# CT_Metering_Assignment-V_33_error_checke.net
KiCad netlist of a schematic drawn in EAGLE
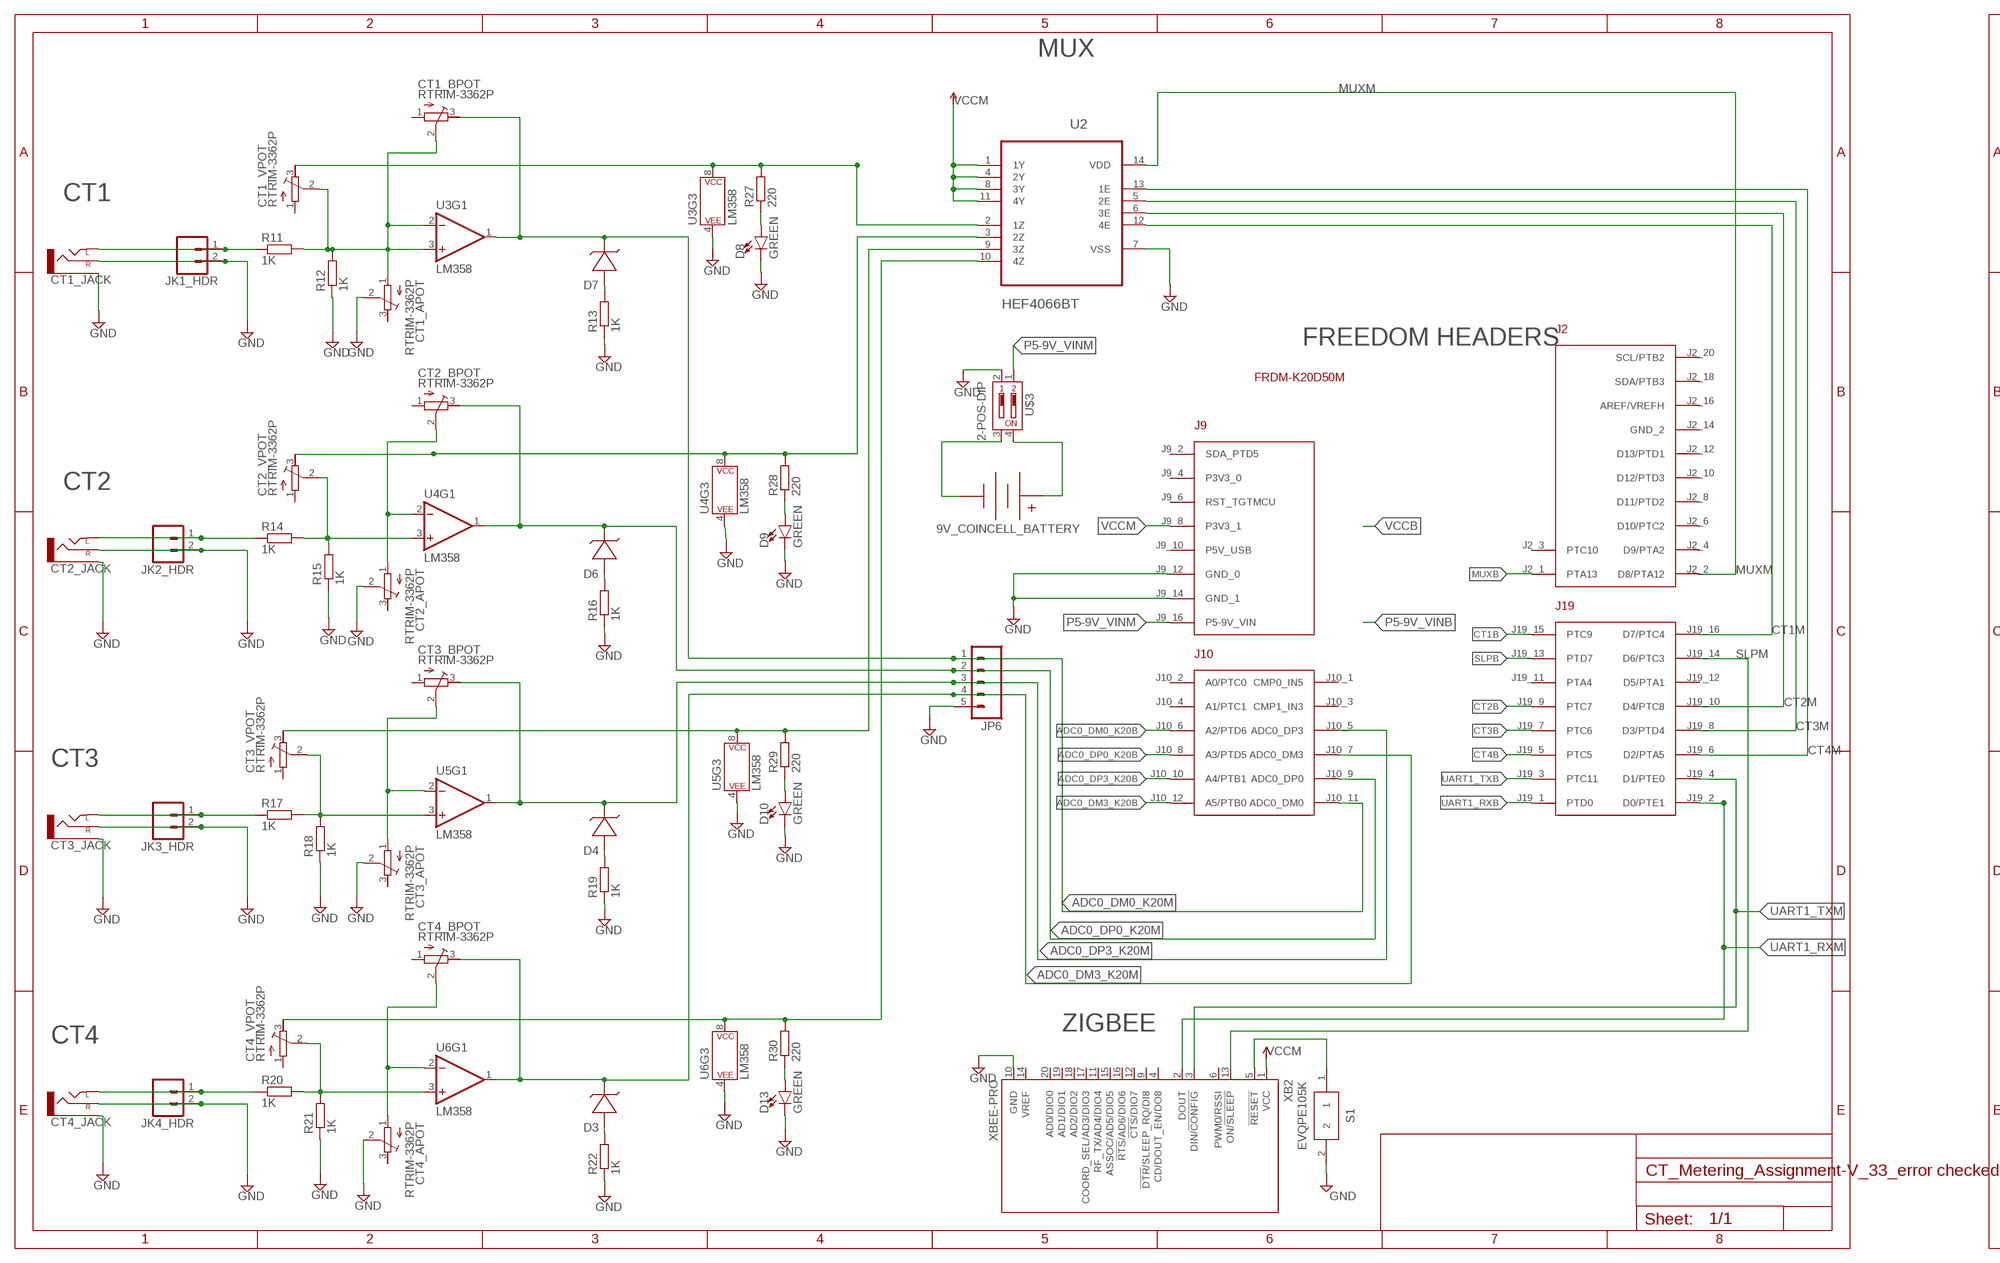
[diagram p0: schematic, sheet 1, part 1 of 2]
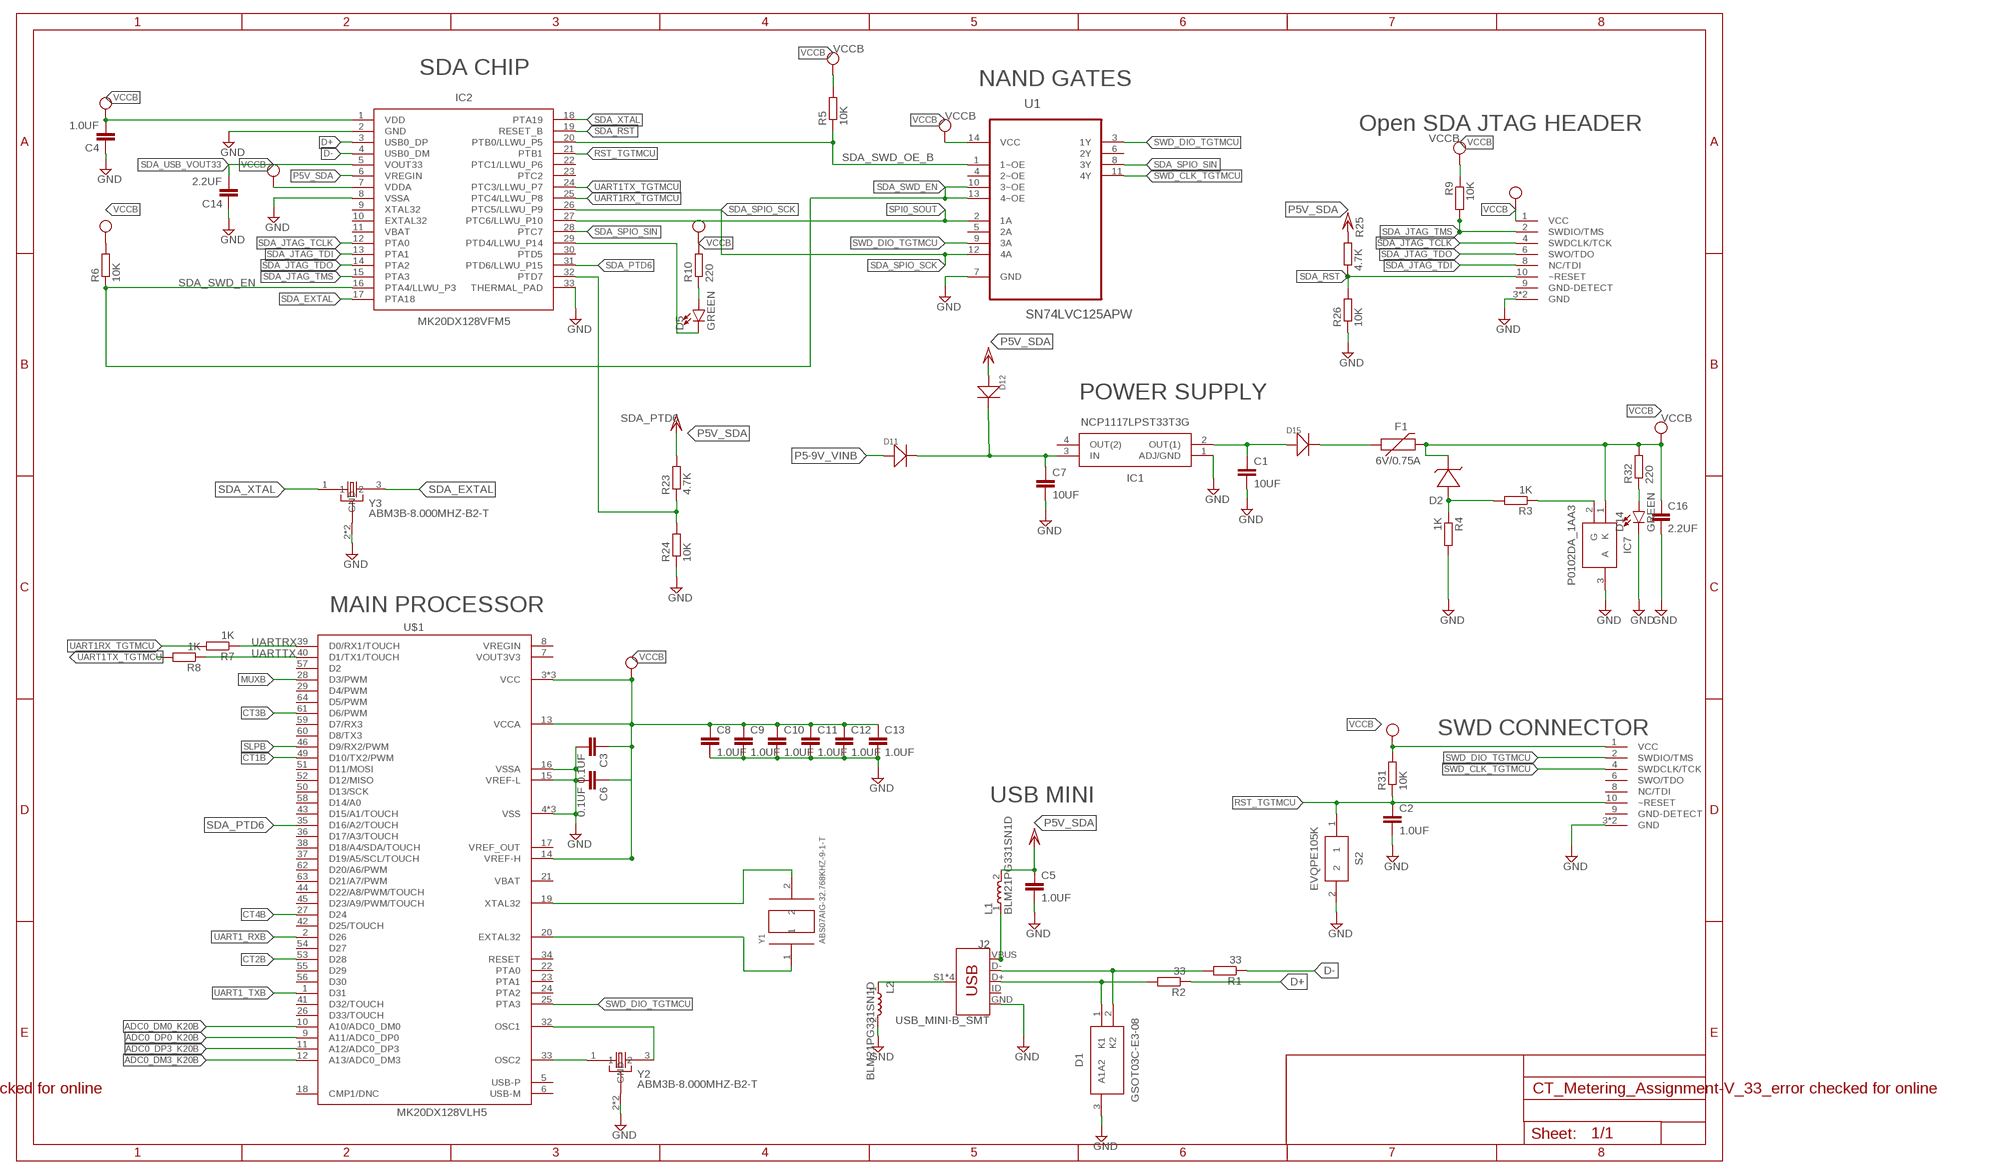
[diagram p1: schematic, sheet 1, part 2 of 2]

(export (version "E")
  (design (tool "Eeschema 10.0.6"))
  (components
    (comp (ref "9V_COINCELL_BATTERY")
      (value "BC9VPC")
      (footprint "eagle-import:BC9VPC")
      (libsource (lib "eagle-import") (part "BC9VPC"))
    )
    (comp (ref "C1")
      (value "10UF")
      (footprint "eagle-import:C1210")
      (libsource (lib "eagle-import") (part "CC1210"))
    )
    (comp (ref "C2")
      (value "1.0UF")
      (footprint "eagle-import:C1210")
      (libsource (lib "eagle-import") (part "CC1210"))
    )
    (comp (ref "C3")
      (value "0.1UF")
      (footprint "eagle-import:C1210")
      (libsource (lib "eagle-import") (part "CC1210"))
    )
    (comp (ref "C4")
      (value "1.0UF")
      (footprint "eagle-import:C1210")
      (libsource (lib "eagle-import") (part "CC1210"))
    )
    (comp (ref "C5")
      (value "1.0UF")
      (footprint "eagle-import:C1210")
      (libsource (lib "eagle-import") (part "CC1210"))
    )
    (comp (ref "C6")
      (value "0.1UF")
      (footprint "eagle-import:C1210")
      (libsource (lib "eagle-import") (part "CC1210"))
    )
    (comp (ref "C7")
      (value "10UF")
      (footprint "eagle-import:C1210")
      (libsource (lib "eagle-import") (part "CC1210"))
    )
    (comp (ref "C8")
      (value "1.0UF")
      (footprint "eagle-import:C1210")
      (libsource (lib "eagle-import") (part "CC1210"))
    )
    (comp (ref "C9")
      (value "1.0UF")
      (footprint "eagle-import:C1210")
      (libsource (lib "eagle-import") (part "CC1210"))
    )
    (comp (ref "C10")
      (value "1.0UF")
      (footprint "eagle-import:C1210")
      (libsource (lib "eagle-import") (part "CC1210"))
    )
    (comp (ref "C11")
      (value "1.0UF")
      (footprint "eagle-import:C1210")
      (libsource (lib "eagle-import") (part "CC1210"))
    )
    (comp (ref "C12")
      (value "1.0UF")
      (footprint "eagle-import:C1210")
      (libsource (lib "eagle-import") (part "CC1210"))
    )
    (comp (ref "C13")
      (value "1.0UF")
      (footprint "eagle-import:C1210")
      (libsource (lib "eagle-import") (part "CC1210"))
    )
    (comp (ref "C14")
      (value "2.2UF")
      (footprint "eagle-import:C1210")
      (libsource (lib "eagle-import") (part "CC1210"))
    )
    (comp (ref "C16")
      (value "2.2UF")
      (footprint "eagle-import:C1210")
      (libsource (lib "eagle-import") (part "CC1210"))
    )
    (comp (ref "CT1_APOT")
      (value "RTRIM-3362P")
      (footprint "eagle-import:RTRIM3362P")
      (libsource (lib "eagle-import") (part "RTRIM-3362P"))
    )
    (comp (ref "CT1_BPOT")
      (value "RTRIM-3362P")
      (footprint "eagle-import:RTRIM3362P")
      (libsource (lib "eagle-import") (part "RTRIM-3362P"))
    )
    (comp (ref "CT1_JACK")
      (value "AUDIO-JACKPTH")
      (footprint "eagle-import:AUDIO-JACK")
      (libsource (lib "eagle-import") (part "AUDIO-JACKPTH"))
    )
    (comp (ref "CT1_VPOT")
      (value "RTRIM-3362P")
      (footprint "eagle-import:RTRIM3362P")
      (libsource (lib "eagle-import") (part "RTRIM-3362P"))
    )
    (comp (ref "CT2_APOT")
      (value "RTRIM-3362P")
      (footprint "eagle-import:RTRIM3362P")
      (libsource (lib "eagle-import") (part "RTRIM-3362P"))
    )
    (comp (ref "CT2_BPOT")
      (value "RTRIM-3362P")
      (footprint "eagle-import:RTRIM3362P")
      (libsource (lib "eagle-import") (part "RTRIM-3362P"))
    )
    (comp (ref "CT2_JACK")
      (value "AUDIO-JACKPTH")
      (footprint "eagle-import:AUDIO-JACK")
      (libsource (lib "eagle-import") (part "AUDIO-JACKPTH"))
    )
    (comp (ref "CT2_VPOT")
      (value "RTRIM-3362P")
      (footprint "eagle-import:RTRIM3362P")
      (libsource (lib "eagle-import") (part "RTRIM-3362P"))
    )
    (comp (ref "CT3_APOT")
      (value "RTRIM-3362P")
      (footprint "eagle-import:RTRIM3362P")
      (libsource (lib "eagle-import") (part "RTRIM-3362P"))
    )
    (comp (ref "CT3_BPOT")
      (value "RTRIM-3362P")
      (footprint "eagle-import:RTRIM3362P")
      (libsource (lib "eagle-import") (part "RTRIM-3362P"))
    )
    (comp (ref "CT3_JACK")
      (value "AUDIO-JACKPTH")
      (footprint "eagle-import:AUDIO-JACK")
      (libsource (lib "eagle-import") (part "AUDIO-JACKPTH"))
    )
    (comp (ref "CT3_VPOT")
      (value "RTRIM-3362P")
      (footprint "eagle-import:RTRIM3362P")
      (libsource (lib "eagle-import") (part "RTRIM-3362P"))
    )
    (comp (ref "CT4_APOT")
      (value "RTRIM-3362P")
      (footprint "eagle-import:RTRIM3362P")
      (libsource (lib "eagle-import") (part "RTRIM-3362P"))
    )
    (comp (ref "CT4_BPOT")
      (value "RTRIM-3362P")
      (footprint "eagle-import:RTRIM3362P")
      (libsource (lib "eagle-import") (part "RTRIM-3362P"))
    )
    (comp (ref "CT4_JACK")
      (value "AUDIO-JACKPTH")
      (footprint "eagle-import:AUDIO-JACK")
      (libsource (lib "eagle-import") (part "AUDIO-JACKPTH"))
    )
    (comp (ref "CT4_VPOT")
      (value "RTRIM-3362P")
      (footprint "eagle-import:RTRIM3362P")
      (libsource (lib "eagle-import") (part "RTRIM-3362P"))
    )
    (comp (ref "D1")
      (value "GSOT03C-E3-08")
      (footprint "eagle-import:SOT100P248X115-3N")
      (fields (field (name "RS_PART_NUMBER") "6997957"))
      (libsource (lib "eagle-import") (part "GSOT03C-E3-08"))
    )
    (comp (ref "D2")
      (value "ZENER")
      (footprint "eagle-import:SOD123")
      (libsource (lib "eagle-import") (part "ZENER"))
    )
    (comp (ref "D3")
      (value "ZENER")
      (footprint "eagle-import:SOD123")
      (libsource (lib "eagle-import") (part "ZENER"))
    )
    (comp (ref "D4")
      (value "ZENER")
      (footprint "eagle-import:SOD123")
      (libsource (lib "eagle-import") (part "ZENER"))
    )
    (comp (ref "D5")
      (value "GREEN")
      (footprint "eagle-import:LED-0603")
      (libsource (lib "eagle-import") (part "LED-GREEN0603"))
    )
    (comp (ref "D6")
      (value "ZENER")
      (footprint "eagle-import:SOD123")
      (libsource (lib "eagle-import") (part "ZENER"))
    )
    (comp (ref "D7")
      (value "ZENER")
      (footprint "eagle-import:SOD123")
      (libsource (lib "eagle-import") (part "ZENER"))
    )
    (comp (ref "D8")
      (value "GREEN")
      (footprint "eagle-import:LED-0603")
      (libsource (lib "eagle-import") (part "LED-GREEN0603"))
    )
    (comp (ref "D9")
      (value "GREEN")
      (footprint "eagle-import:LED-0603")
      (libsource (lib "eagle-import") (part "LED-GREEN0603"))
    )
    (comp (ref "D10")
      (value "GREEN")
      (footprint "eagle-import:LED-0603")
      (libsource (lib "eagle-import") (part "LED-GREEN0603"))
    )
    (comp (ref "D11")
      (value "20V-1A")
      (footprint "eagle-import:SOD-123")
      (fields (field (name "MPN") "B5819W"))
      (libsource (lib "eagle-import") (part "SMD-DIODE-SCHOTTKY-20V-1A(SOD-123)"))
    )
    (comp (ref "D12")
      (value "20V-1A")
      (footprint "eagle-import:SOD-123")
      (fields (field (name "MPN") "B5819W"))
      (libsource (lib "eagle-import") (part "SMD-DIODE-SCHOTTKY-20V-1A(SOD-123)"))
    )
    (comp (ref "D13")
      (value "GREEN")
      (footprint "eagle-import:LED-0603")
      (libsource (lib "eagle-import") (part "LED-GREEN0603"))
    )
    (comp (ref "D14")
      (value "GREEN")
      (footprint "eagle-import:LED-0603")
      (libsource (lib "eagle-import") (part "LED-GREEN0603"))
    )
    (comp (ref "D15")
      (value "20V-1A")
      (footprint "eagle-import:SOD-123")
      (fields (field (name "MPN") "B5819W"))
      (libsource (lib "eagle-import") (part "SMD-DIODE-SCHOTTKY-20V-1A(SOD-123)"))
    )
    (comp (ref "F1")
      (value "6V/0.75A")
      (footprint "eagle-import:1206")
      (libsource (lib "eagle-import") (part "PPTC_THREE-QUARTER-AMP"))
    )
    (comp (ref "FRDM1")
      (value "FRDM-K20D50M")
      (footprint "eagle-import:FRDM-K20D50M")
      (libsource (lib "eagle-import") (part "FRDM-K20D50M"))
    )
    (comp (ref "IC1")
      (value "NCP1117LPST33T3G")
      (footprint "eagle-import:SOT230P700X180-4N")
      (fields (field (name "RS_PART_NUMBER") "1245347"))
      (libsource (lib "eagle-import") (part "NCP1117LPST33T3G"))
    )
    (comp (ref "IC2")
      (value "MK20DX128VFM5")
      (footprint "eagle-import:SOT617-14")
      (fields (field (name "RS_PART_NUMBER") "8181223"))
      (libsource (lib "eagle-import") (part "MK20DX128VFM5"))
    )
    (comp (ref "IC7")
      (value "P0102DA_1AA3")
      (footprint "eagle-import:TO-92")
      (fields
        (field (name "MANUFACTURER_PART_NUMBER") "P0102DA 1AA3")
        (field (name "RS_PART_NUMBER") "7142647")
      )
      (libsource (lib "eagle-import") (part "P0102DA_1AA3"))
    )
    (comp (ref "J2")
      (value "USB_MINI-B_SMT")
      (footprint "eagle-import:USB-MINIB")
      (libsource (lib "eagle-import") (part "USB_MINI-B_SMT"))
    )
    (comp (ref "JK1_HDR")
      (value "M02PTH")
      (footprint "eagle-import:1X02")
      (libsource (lib "eagle-import") (part "M02PTH"))
    )
    (comp (ref "JK2_HDR")
      (value "M02PTH")
      (footprint "eagle-import:1X02")
      (libsource (lib "eagle-import") (part "M02PTH"))
    )
    (comp (ref "JK3_HDR")
      (value "M02PTH")
      (footprint "eagle-import:1X02")
      (libsource (lib "eagle-import") (part "M02PTH"))
    )
    (comp (ref "JK4_HDR")
      (value "M02PTH")
      (footprint "eagle-import:1X02")
      (libsource (lib "eagle-import") (part "M02PTH"))
    )
    (comp (ref "JP6")
      (value "M05PTH")
      (footprint "eagle-import:1X05")
      (libsource (lib "eagle-import") (part "M05PTH"))
    )
    (comp (ref "L1")
      (value "BLM21PG331SN1D")
      (footprint "eagle-import:INDC2012X87")
      (fields (field (name "MF") "Murata"))
      (libsource (lib "eagle-import") (part "BLM21PG331SN1D"))
    )
    (comp (ref "L2")
      (value "BLM21PG331SN1D")
      (footprint "eagle-import:INDC2012X87")
      (fields (field (name "MF") "Murata"))
      (libsource (lib "eagle-import") (part "BLM21PG331SN1D"))
    )
    (comp (ref "R1")
      (value "33")
      (footprint "eagle-import:PRL1632")
      (libsource (lib "eagle-import") (part "R-EU_PRL1632"))
    )
    (comp (ref "R2")
      (value "33")
      (footprint "eagle-import:PRL1632")
      (libsource (lib "eagle-import") (part "R-EU_PRL1632"))
    )
    (comp (ref "R3")
      (value "1K")
      (footprint "eagle-import:PRL1632")
      (libsource (lib "eagle-import") (part "R-EU_PRL1632"))
    )
    (comp (ref "R4")
      (value "1K")
      (footprint "eagle-import:PRL1632")
      (libsource (lib "eagle-import") (part "R-EU_PRL1632"))
    )
    (comp (ref "R5")
      (value "10K")
      (footprint "eagle-import:PRL1632")
      (libsource (lib "eagle-import") (part "R-EU_PRL1632"))
    )
    (comp (ref "R6")
      (value "10K")
      (footprint "eagle-import:PRL1632")
      (libsource (lib "eagle-import") (part "R-EU_PRL1632"))
    )
    (comp (ref "R7")
      (value "1K")
      (footprint "eagle-import:PRL1632")
      (libsource (lib "eagle-import") (part "R-EU_PRL1632"))
    )
    (comp (ref "R8")
      (value "1K")
      (footprint "eagle-import:PRL1632")
      (libsource (lib "eagle-import") (part "R-EU_PRL1632"))
    )
    (comp (ref "R9")
      (value "10K")
      (footprint "eagle-import:PRL1632")
      (libsource (lib "eagle-import") (part "R-EU_PRL1632"))
    )
    (comp (ref "R10")
      (value "220")
      (footprint "eagle-import:PRL1632")
      (libsource (lib "eagle-import") (part "R-EU_PRL1632"))
    )
    (comp (ref "R11")
      (value "1K")
      (footprint "eagle-import:PRL1632")
      (libsource (lib "eagle-import") (part "R-EU_PRL1632"))
    )
    (comp (ref "R12")
      (value "1K")
      (footprint "eagle-import:PRL1632")
      (libsource (lib "eagle-import") (part "R-EU_PRL1632"))
    )
    (comp (ref "R13")
      (value "1K")
      (footprint "eagle-import:PRL1632")
      (libsource (lib "eagle-import") (part "R-EU_PRL1632"))
    )
    (comp (ref "R14")
      (value "1K")
      (footprint "eagle-import:PRL1632")
      (libsource (lib "eagle-import") (part "R-EU_PRL1632"))
    )
    (comp (ref "R15")
      (value "1K")
      (footprint "eagle-import:PRL1632")
      (libsource (lib "eagle-import") (part "R-EU_PRL1632"))
    )
    (comp (ref "R16")
      (value "1K")
      (footprint "eagle-import:PRL1632")
      (libsource (lib "eagle-import") (part "R-EU_PRL1632"))
    )
    (comp (ref "R17")
      (value "1K")
      (footprint "eagle-import:PRL1632")
      (libsource (lib "eagle-import") (part "R-EU_PRL1632"))
    )
    (comp (ref "R18")
      (value "1K")
      (footprint "eagle-import:PRL1632")
      (libsource (lib "eagle-import") (part "R-EU_PRL1632"))
    )
    (comp (ref "R19")
      (value "1K")
      (footprint "eagle-import:PRL1632")
      (libsource (lib "eagle-import") (part "R-EU_PRL1632"))
    )
    (comp (ref "R20")
      (value "1K")
      (footprint "eagle-import:PRL1632")
      (libsource (lib "eagle-import") (part "R-EU_PRL1632"))
    )
    (comp (ref "R21")
      (value "1K")
      (footprint "eagle-import:PRL1632")
      (libsource (lib "eagle-import") (part "R-EU_PRL1632"))
    )
    (comp (ref "R22")
      (value "1K")
      (footprint "eagle-import:PRL1632")
      (libsource (lib "eagle-import") (part "R-EU_PRL1632"))
    )
    (comp (ref "R23")
      (value "4.7K")
      (footprint "eagle-import:PRL1632")
      (libsource (lib "eagle-import") (part "R-EU_PRL1632"))
    )
    (comp (ref "R24")
      (value "10K")
      (footprint "eagle-import:PRL1632")
      (libsource (lib "eagle-import") (part "R-EU_PRL1632"))
    )
    (comp (ref "R25")
      (value "4.7K")
      (footprint "eagle-import:PRL1632")
      (libsource (lib "eagle-import") (part "R-EU_PRL1632"))
    )
    (comp (ref "R26")
      (value "10K")
      (footprint "eagle-import:PRL1632")
      (libsource (lib "eagle-import") (part "R-EU_PRL1632"))
    )
    (comp (ref "R27")
      (value "220")
      (footprint "eagle-import:PRL1632")
      (libsource (lib "eagle-import") (part "R-EU_PRL1632"))
    )
    (comp (ref "R28")
      (value "220")
      (footprint "eagle-import:PRL1632")
      (libsource (lib "eagle-import") (part "R-EU_PRL1632"))
    )
    (comp (ref "R29")
      (value "220")
      (footprint "eagle-import:PRL1632")
      (libsource (lib "eagle-import") (part "R-EU_PRL1632"))
    )
    (comp (ref "R30")
      (value "220")
      (footprint "eagle-import:PRL1632")
      (libsource (lib "eagle-import") (part "R-EU_PRL1632"))
    )
    (comp (ref "R31")
      (value "10K")
      (footprint "eagle-import:PRL1632")
      (libsource (lib "eagle-import") (part "R-EU_PRL1632"))
    )
    (comp (ref "R32")
      (value "220")
      (footprint "eagle-import:PRL1632")
      (libsource (lib "eagle-import") (part "R-EU_PRL1632"))
    )
    (comp (ref "S1")
      (value "EVQPE105K")
      (footprint "eagle-import:EVQPE1")
      (fields (field (name "RS_PART_NUMBER") "7561669"))
      (libsource (lib "eagle-import") (part "EVQPE105K"))
    )
    (comp (ref "S2")
      (value "EVQPE105K")
      (footprint "eagle-import:EVQPE1")
      (fields (field (name "RS_PART_NUMBER") "7561669"))
      (libsource (lib "eagle-import") (part "EVQPE105K"))
    )
    (comp (ref "U$1")
      (value "MK20DX128VLH5")
      (footprint "eagle-import:QFP50P1200X1200X160-64N")
      (fields (field (name "MF") "NXP Semiconductors"))
      (libsource (lib "eagle-import") (part "MK20DX128VLH5"))
    )
    (comp (ref "U$2")
      (value "2X5_0.05\"_CORTEX_DEBUGTH_NOKEY_UNSHROUDED")
      (footprint "eagle-import:2X5_0.05__TH_NS")
      (libsource (lib "eagle-import") (part "2X5_0.05{dblquote}_CORTEX_DEBUGTH_NOKEY_UNSHROUDED"))
    )
    (comp (ref "U$3")
      (value "2-POS-DIP")
      (footprint "eagle-import:CHS-02A")
      (libsource (lib "eagle-import") (part "2-POS-DIP"))
    )
    (comp (ref "U$6")
      (value "SWD HHEADER")
      (footprint "eagle-import:2X5_0.05__TH_NS")
      (libsource (lib "eagle-import") (part "2X5_0.05{dblquote}_CORTEX_DEBUGTH_NOKEY_UNSHROUDED"))
    )
    (comp (ref "U1")
      (value "SN74LVC125APW")
      (footprint "eagle-import:SOP65P640X120-14N")
      (fields (field (name "MF") "Texas Instruments"))
      (libsource (lib "eagle-import") (part "SN74LVC125APW"))
    )
    (comp (ref "U2")
      (value "HEF4066BT")
      (footprint "eagle-import:SOIC127P600X175-14N")
      (fields (field (name "MF") "NXP Semiconductors"))
      (libsource (lib "eagle-import") (part "HEF4066BT"))
    )
    (comp (ref "U3")
      (value "LM358")
      (footprint "eagle-import:DIP08")
      (libsource (lib "eagle-import") (part "LM358"))
    )
    (comp (ref "U4")
      (value "LM358")
      (footprint "eagle-import:DIP08")
      (libsource (lib "eagle-import") (part "LM358"))
    )
    (comp (ref "U5")
      (value "LM358")
      (footprint "eagle-import:DIP08")
      (libsource (lib "eagle-import") (part "LM358"))
    )
    (comp (ref "U6")
      (value "LM358")
      (footprint "eagle-import:DIP08")
      (libsource (lib "eagle-import") (part "LM358"))
    )
    (comp (ref "XB2")
      (value "XBEE-PRO")
      (footprint "eagle-import:XBEE-PRO")
      (fields (field (name "MPN") "XBP24-AWI-001"))
      (libsource (lib "eagle-import") (part "XBEE-PRO"))
    )
    (comp (ref "Y1")
      (value "ABS07AIG-32.768KHZ-9-1-T")
      (footprint "eagle-import:XTAL320X150X90")
      (fields (field (name "MF") "Abracon"))
      (libsource (lib "eagle-import") (part "ABS07AIG-32.768KHZ-9-1-T"))
    )
    (comp (ref "Y2")
      (value "ABM3B-8.000MHZ-B2-T")
      (footprint "eagle-import:OSCSC500X320X110-4N")
      (fields (field (name "MF") "Abracon"))
      (libsource (lib "eagle-import") (part "ABM3B-8.000MHZ-B2-T"))
    )
    (comp (ref "Y3")
      (value "ABM3B-8.000MHZ-B2-T")
      (footprint "eagle-import:OSCSC500X320X110-4N")
      (fields (field (name "MF") "Abracon"))
      (libsource (lib "eagle-import") (part "ABM3B-8.000MHZ-B2-T"))
    )
  )
  (nets
    (net (code "1") (name "/CT1M") (class "Default")
      (node (ref "FRDM1") (pin "J19_16") (pinfunction "D7/PTC4_J19_16") (pintype "bidirectional"))
      (node (ref "U2") (pin "12") (pinfunction "4E_12") (pintype "input"))
    )
    (net (code "2") (name "/CT2M") (class "Default")
      (node (ref "FRDM1") (pin "J19_10") (pinfunction "D4/PTC8_J19_10") (pintype "bidirectional"))
      (node (ref "U2") (pin "6") (pinfunction "3E_6") (pintype "input"))
    )
    (net (code "3") (name "/CT3M") (class "Default")
      (node (ref "FRDM1") (pin "J19_8") (pinfunction "D3/PTD4_J19_8") (pintype "bidirectional"))
      (node (ref "U2") (pin "5") (pinfunction "2E_5") (pintype "input"))
    )
    (net (code "4") (name "/CT4M") (class "Default")
      (node (ref "FRDM1") (pin "J19_6") (pinfunction "D2/PTA5_J19_6") (pintype "bidirectional"))
      (node (ref "U2") (pin "13") (pinfunction "1E_13") (pintype "input"))
    )
    (net (code "5") (name "/MUXM") (class "Default")
      (node (ref "FRDM1") (pin "J2_2") (pinfunction "D8/PTA12_J2_2") (pintype "bidirectional"))
      (node (ref "U2") (pin "14") (pinfunction "VDD_14") (pintype "power_in"))
    )
    (net (code "6") (name "/SDA_SWD_OE_B") (class "Default")
      (node (ref "IC2") (pin "20") (pinfunction "PTB0/LLWU_P5_20") (pintype "passive"))
      (node (ref "R5") (pin "1") (pinfunction "1_1") (pintype "passive"))
      (node (ref "U1") (pin "1") (pinfunction "1~{OE}_1") (pintype "input"))
    )
    (net (code "7") (name "/SLPM") (class "Default")
      (node (ref "FRDM1") (pin "J19_14") (pinfunction "D6/PTC3_J19_14") (pintype "bidirectional"))
      (node (ref "XB2") (pin "13") (pinfunction "ON/~{SLEEP}_13") (pintype "output"))
    )
    (net (code "8") (name "/UARTRX") (class "Default")
      (node (ref "R7") (pin "1") (pinfunction "1_1") (pintype "passive"))
      (node (ref "U$1") (pin "39") (pinfunction "D0/RX1/TOUCH_39") (pintype "bidirectional"))
    )
    (net (code "9") (name "/UARTTX") (class "Default")
      (node (ref "R8") (pin "1") (pinfunction "1_1") (pintype "passive"))
      (node (ref "U$1") (pin "40") (pinfunction "D1/TX1/TOUCH_40") (pintype "bidirectional"))
    )
    (net (code "10") (name "ADC0_DM0_K20B") (class "Default")
      (node (ref "FRDM1") (pin "J10_6") (pinfunction "A2/PTD6_J10_6") (pintype "bidirectional"))
      (node (ref "U$1") (pin "10") (pinfunction "A10/ADC0_DM0_10") (pintype "bidirectional"))
    )
    (net (code "11") (name "ADC0_DM0_K20M") (class "Default")
      (node (ref "CT1_BPOT") (pin "3") (pinfunction "3_3") (pintype "passive"))
      (node (ref "D7") (pin "C") (pinfunction "-_C") (pintype "passive"))
      (node (ref "FRDM1") (pin "J10_11") (pinfunction "ADC0_DM0_J10_11") (pintype "bidirectional"))
      (node (ref "JP6") (pin "1") (pinfunction "1_1") (pintype "passive"))
      (node (ref "U3") (pin "1") (pinfunction "OUT_1") (pintype "output"))
    )
    (net (code "12") (name "ADC0_DM3_K20B") (class "Default")
      (node (ref "FRDM1") (pin "J10_12") (pinfunction "A5/PTB0_J10_12") (pintype "bidirectional"))
      (node (ref "U$1") (pin "12") (pinfunction "A13/ADC0_DM3_12") (pintype "bidirectional"))
    )
    (net (code "13") (name "ADC0_DM3_K20M") (class "Default")
      (node (ref "CT4_BPOT") (pin "3") (pinfunction "3_3") (pintype "passive"))
      (node (ref "D3") (pin "C") (pinfunction "-_C") (pintype "passive"))
      (node (ref "FRDM1") (pin "J10_7") (pinfunction "ADC0_DM3_J10_7") (pintype "bidirectional"))
      (node (ref "JP6") (pin "4") (pinfunction "4_4") (pintype "passive"))
      (node (ref "U6") (pin "1") (pinfunction "OUT_1") (pintype "output"))
    )
    (net (code "14") (name "ADC0_DP0_K20B") (class "Default")
      (node (ref "FRDM1") (pin "J10_8") (pinfunction "A3/PTD5_J10_8") (pintype "bidirectional"))
      (node (ref "U$1") (pin "9") (pinfunction "A11/ADC0_DP0_9") (pintype "bidirectional"))
    )
    (net (code "15") (name "ADC0_DP0_K20M") (class "Default")
      (node (ref "CT2_BPOT") (pin "3") (pinfunction "3_3") (pintype "passive"))
      (node (ref "D6") (pin "C") (pinfunction "-_C") (pintype "passive"))
      (node (ref "FRDM1") (pin "J10_9") (pinfunction "ADC0_DP0_J10_9") (pintype "bidirectional"))
      (node (ref "JP6") (pin "2") (pinfunction "2_2") (pintype "passive"))
      (node (ref "U4") (pin "1") (pinfunction "OUT_1") (pintype "output"))
    )
    (net (code "16") (name "ADC0_DP3_K20B") (class "Default")
      (node (ref "FRDM1") (pin "J10_10") (pinfunction "A4/PTB1_J10_10") (pintype "bidirectional"))
      (node (ref "U$1") (pin "11") (pinfunction "A12/ADC0_DP3_11") (pintype "bidirectional"))
    )
    (net (code "17") (name "ADC0_DP3_K20M") (class "Default")
      (node (ref "CT3_BPOT") (pin "3") (pinfunction "3_3") (pintype "passive"))
      (node (ref "D4") (pin "C") (pinfunction "-_C") (pintype "passive"))
      (node (ref "FRDM1") (pin "J10_5") (pinfunction "ADC0_DP3_J10_5") (pintype "bidirectional"))
      (node (ref "JP6") (pin "3") (pinfunction "3_3") (pintype "passive"))
      (node (ref "U5") (pin "1") (pinfunction "OUT_1") (pintype "output"))
    )
    (net (code "18") (name "CT1B") (class "Default")
      (node (ref "FRDM1") (pin "J19_15") (pinfunction "PTC9_J19_15") (pintype "bidirectional"))
      (node (ref "U$1") (pin "49") (pinfunction "D10/TX2/PWM_49") (pintype "bidirectional"))
    )
    (net (code "19") (name "CT2B") (class "Default")
      (node (ref "FRDM1") (pin "J19_9") (pinfunction "PTC7_J19_9") (pintype "bidirectional"))
      (node (ref "U$1") (pin "53") (pinfunction "D28_53") (pintype "bidirectional"))
    )
    (net (code "20") (name "CT3B") (class "Default")
      (node (ref "FRDM1") (pin "J19_7") (pinfunction "PTC6_J19_7") (pintype "bidirectional"))
      (node (ref "U$1") (pin "61") (pinfunction "D6/PWM_61") (pintype "bidirectional"))
    )
    (net (code "21") (name "CT4B") (class "Default")
      (node (ref "FRDM1") (pin "J19_5") (pinfunction "PTC5_J19_5") (pintype "bidirectional"))
      (node (ref "U$1") (pin "27") (pinfunction "D24_27") (pintype "bidirectional"))
    )
    (net (code "22") (name "D+") (class "Default")
      (node (ref "IC2") (pin "3") (pinfunction "USB0_DP_3") (pintype "passive"))
      (node (ref "R2") (pin "1") (pinfunction "1_1") (pintype "passive"))
    )
    (net (code "23") (name "D-") (class "Default")
      (node (ref "IC2") (pin "4") (pinfunction "USB0_DM_4") (pintype "passive"))
      (node (ref "R1") (pin "1") (pinfunction "1_1") (pintype "passive"))
    )
    (net (code "24") (name "GND") (class "Default")
      (node (ref "C1") (pin "2") (pinfunction "2_2") (pintype "passive"))
      (node (ref "C10") (pin "2") (pinfunction "2_2") (pintype "passive"))
      (node (ref "C11") (pin "2") (pinfunction "2_2") (pintype "passive"))
      (node (ref "C12") (pin "2") (pinfunction "2_2") (pintype "passive"))
      (node (ref "C13") (pin "2") (pinfunction "2_2") (pintype "passive"))
      (node (ref "C14") (pin "1") (pinfunction "1_1") (pintype "passive"))
      (node (ref "C16") (pin "2") (pinfunction "2_2") (pintype "passive"))
      (node (ref "C2") (pin "2") (pinfunction "2_2") (pintype "passive"))
      (node (ref "C3") (pin "2") (pinfunction "2_2") (pintype "passive"))
      (node (ref "C4") (pin "1") (pinfunction "1_1") (pintype "passive"))
      (node (ref "C5") (pin "2") (pinfunction "2_2") (pintype "passive"))
      (node (ref "C6") (pin "2") (pinfunction "2_2") (pintype "passive"))
      (node (ref "C7") (pin "2") (pinfunction "2_2") (pintype "passive"))
      (node (ref "C8") (pin "2") (pinfunction "2_2") (pintype "passive"))
      (node (ref "C9") (pin "2") (pinfunction "2_2") (pintype "passive"))
      (node (ref "CT1_APOT") (pin "2") (pinfunction "2_2") (pintype "passive"))
      (node (ref "CT1_JACK") (pin "RING") (pinfunction "RIGHT_RING") (pintype "bidirectional"))
      (node (ref "CT1_JACK") (pin "SLEEVE") (pinfunction "SLEEVE_SLEEVE") (pintype "bidirectional"))
      (node (ref "CT2_APOT") (pin "2") (pinfunction "2_2") (pintype "passive"))
      (node (ref "CT2_JACK") (pin "RING") (pinfunction "RIGHT_RING") (pintype "bidirectional"))
      (node (ref "CT2_JACK") (pin "SLEEVE") (pinfunction "SLEEVE_SLEEVE") (pintype "bidirectional"))
      (node (ref "CT3_APOT") (pin "2") (pinfunction "2_2") (pintype "passive"))
      (node (ref "CT3_JACK") (pin "RING") (pinfunction "RIGHT_RING") (pintype "bidirectional"))
      (node (ref "CT3_JACK") (pin "SLEEVE") (pinfunction "SLEEVE_SLEEVE") (pintype "bidirectional"))
      (node (ref "CT4_APOT") (pin "2") (pinfunction "2_2") (pintype "passive"))
      (node (ref "CT4_JACK") (pin "RING") (pinfunction "RIGHT_RING") (pintype "bidirectional"))
      (node (ref "CT4_JACK") (pin "SLEEVE") (pinfunction "SLEEVE_SLEEVE") (pintype "bidirectional"))
      (node (ref "D1") (pin "3") (pinfunction "A1A2_3") (pintype "passive"))
      (node (ref "D10") (pin "C") (pinfunction "C_C") (pintype "passive"))
      (node (ref "D13") (pin "C") (pinfunction "C_C") (pintype "passive"))
      (node (ref "D14") (pin "C") (pinfunction "C_C") (pintype "passive"))
      (node (ref "D8") (pin "C") (pinfunction "C_C") (pintype "passive"))
      (node (ref "D9") (pin "C") (pinfunction "C_C") (pintype "passive"))
      (node (ref "FRDM1") (pin "J9_12") (pinfunction "GND_0_J9_12") (pintype "bidirectional"))
      (node (ref "FRDM1") (pin "J9_14") (pinfunction "GND_1_J9_14") (pintype "bidirectional"))
      (node (ref "IC1") (pin "1") (pinfunction "ADJ/GND_1") (pintype "power_in"))
      (node (ref "IC2") (pin "2") (pinfunction "GND_2") (pintype "passive"))
      (node (ref "IC2") (pin "33") (pinfunction "THERMAL_PAD_33") (pintype "passive"))
      (node (ref "IC2") (pin "8") (pinfunction "VSSA_8") (pintype "passive"))
      (node (ref "IC7") (pin "3") (pinfunction "A_3") (pintype "passive"))
      (node (ref "J2") (pin "GND") (pinfunction "GND_GND") (pintype "power_in"))
      (node (ref "JK1_HDR") (pin "2") (pinfunction "2_2") (pintype "passive"))
      (node (ref "JK2_HDR") (pin "2") (pinfunction "2_2") (pintype "passive"))
      (node (ref "JK3_HDR") (pin "2") (pinfunction "2_2") (pintype "passive"))
      (node (ref "JK4_HDR") (pin "2") (pinfunction "2_2") (pintype "passive"))
      (node (ref "JP6") (pin "5") (pinfunction "5_5") (pintype "passive"))
      (node (ref "L2") (pin "2") (pinfunction "2_2") (pintype "passive"))
      (node (ref "R12") (pin "1") (pinfunction "1_1") (pintype "passive"))
      (node (ref "R13") (pin "1") (pinfunction "1_1") (pintype "passive"))
      (node (ref "R15") (pin "1") (pinfunction "1_1") (pintype "passive"))
      (node (ref "R16") (pin "1") (pinfunction "1_1") (pintype "passive"))
      (node (ref "R18") (pin "1") (pinfunction "1_1") (pintype "passive"))
      (node (ref "R19") (pin "1") (pinfunction "1_1") (pintype "passive"))
      (node (ref "R21") (pin "1") (pinfunction "1_1") (pintype "passive"))
      (node (ref "R22") (pin "1") (pinfunction "1_1") (pintype "passive"))
      (node (ref "R24") (pin "1") (pinfunction "1_1") (pintype "passive"))
      (node (ref "R26") (pin "1") (pinfunction "1_1") (pintype "passive"))
      (node (ref "R4") (pin "2") (pinfunction "2_2") (pintype "passive"))
      (node (ref "S1") (pin "2") (pinfunction "2_2") (pintype "passive"))
      (node (ref "S2") (pin "2") (pinfunction "2_2") (pintype "passive"))
      (node (ref "U$1") (pin "15") (pinfunction "VREF-L_15") (pintype "bidirectional"))
      (node (ref "U$1") (pin "16") (pinfunction "VSSA_16") (pintype "bidirectional"))
      (node (ref "U$1") (pin "31") (pinfunction "VSS_31") (pintype "bidirectional"))
      (node (ref "U$1") (pin "4") (pinfunction "VSS_4") (pintype "bidirectional"))
      (node (ref "U$1") (pin "47") (pinfunction "VSS_47") (pintype "bidirectional"))
      (node (ref "U$2") (pin "3") (pinfunction "GND_3") (pintype "bidirectional"))
      (node (ref "U$2") (pin "5") (pinfunction "GND_5") (pintype "bidirectional"))
      (node (ref "U$3") (pin "2") (pinfunction "P$2_2") (pintype "bidirectional"))
      (node (ref "U$6") (pin "3") (pinfunction "GND_3") (pintype "bidirectional"))
      (node (ref "U$6") (pin "5") (pinfunction "GND_5") (pintype "bidirectional"))
      (node (ref "U1") (pin "7") (pinfunction "GND_7") (pintype "passive"))
      (node (ref "U2") (pin "7") (pinfunction "VSS_7") (pintype "passive"))
      (node (ref "U3") (pin "4") (pinfunction "P$V-_4") (pintype "bidirectional"))
      (node (ref "U4") (pin "4") (pinfunction "P$V-_4") (pintype "bidirectional"))
      (node (ref "U5") (pin "4") (pinfunction "P$V-_4") (pintype "bidirectional"))
      (node (ref "U6") (pin "4") (pinfunction "P$V-_4") (pintype "bidirectional"))
      (node (ref "XB2") (pin "10") (pinfunction "GND_10") (pintype "power_in"))
      (node (ref "Y2") (pin "2") (pinfunction "GND_2") (pintype "passive"))
      (node (ref "Y2") (pin "4") (pinfunction "GND_4") (pintype "passive"))
      (node (ref "Y3") (pin "2") (pinfunction "GND_2") (pintype "passive"))
      (node (ref "Y3") (pin "4") (pinfunction "GND_4") (pintype "passive"))
    )
    (net (code "25") (name "MUXB") (class "Default")
      (node (ref "FRDM1") (pin "J2_1") (pinfunction "PTA13_J2_1") (pintype "bidirectional"))
      (node (ref "U$1") (pin "28") (pinfunction "D3/PWM_28") (pintype "bidirectional"))
    )
    (net (code "26") (name "Net-(CT1_JACK-LEFT)") (class "Default")
      (node (ref "CT1_JACK") (pin "TIP") (pinfunction "LEFT_TIP") (pintype "bidirectional"))
      (node (ref "JK1_HDR") (pin "1") (pinfunction "1_1") (pintype "passive"))
      (node (ref "R11") (pin "1") (pinfunction "1_1") (pintype "passive"))
    )
    (net (code "27") (name "Net-(CT2_JACK-LEFT)") (class "Default")
      (node (ref "CT2_JACK") (pin "TIP") (pinfunction "LEFT_TIP") (pintype "bidirectional"))
      (node (ref "JK2_HDR") (pin "1") (pinfunction "1_1") (pintype "passive"))
      (node (ref "R14") (pin "1") (pinfunction "1_1") (pintype "passive"))
    )
    (net (code "28") (name "Net-(CT3_JACK-LEFT)") (class "Default")
      (node (ref "CT3_JACK") (pin "TIP") (pinfunction "LEFT_TIP") (pintype "bidirectional"))
      (node (ref "JK3_HDR") (pin "1") (pinfunction "1_1") (pintype "passive"))
      (node (ref "R17") (pin "1") (pinfunction "1_1") (pintype "passive"))
    )
    (net (code "29") (name "Net-(CT4_JACK-LEFT)") (class "Default")
      (node (ref "CT4_JACK") (pin "TIP") (pinfunction "LEFT_TIP") (pintype "bidirectional"))
      (node (ref "JK4_HDR") (pin "1") (pinfunction "1_1") (pintype "passive"))
      (node (ref "R20") (pin "1") (pinfunction "1_1") (pintype "passive"))
    )
    (net (code "30") (name "Net-(D1-K1)") (class "Default")
      (node (ref "D1") (pin "1") (pinfunction "K1_1") (pintype "passive"))
      (node (ref "J2") (pin "D+") (pinfunction "D+_D+") (pintype "bidirectional"))
      (node (ref "R2") (pin "2") (pinfunction "2_2") (pintype "passive"))
    )
    (net (code "31") (name "Net-(D1-K2)") (class "Default")
      (node (ref "D1") (pin "2") (pinfunction "K2_2") (pintype "passive"))
      (node (ref "J2") (pin "D-") (pinfunction "D-_D-") (pintype "bidirectional"))
      (node (ref "R1") (pin "2") (pinfunction "2_2") (pintype "passive"))
    )
    (net (code "32") (name "Net-(D2-+)") (class "Default")
      (node (ref "D2") (pin "A") (pinfunction "+_A") (pintype "passive"))
      (node (ref "R3") (pin "2") (pinfunction "2_2") (pintype "passive"))
      (node (ref "R4") (pin "1") (pinfunction "1_1") (pintype "passive"))
    )
    (net (code "33") (name "Net-(D3-+)") (class "Default")
      (node (ref "D3") (pin "A") (pinfunction "+_A") (pintype "passive"))
      (node (ref "R22") (pin "2") (pinfunction "2_2") (pintype "passive"))
    )
    (net (code "34") (name "Net-(D4-+)") (class "Default")
      (node (ref "D4") (pin "A") (pinfunction "+_A") (pintype "passive"))
      (node (ref "R19") (pin "2") (pinfunction "2_2") (pintype "passive"))
    )
    (net (code "35") (name "Net-(D5-PadA)") (class "Default")
      (node (ref "D5") (pin "A") (pinfunction "A_A") (pintype "passive"))
      (node (ref "R10") (pin "1") (pinfunction "1_1") (pintype "passive"))
    )
    (net (code "36") (name "Net-(D6-+)") (class "Default")
      (node (ref "D6") (pin "A") (pinfunction "+_A") (pintype "passive"))
      (node (ref "R16") (pin "2") (pinfunction "2_2") (pintype "passive"))
    )
    (net (code "37") (name "Net-(D7-+)") (class "Default")
      (node (ref "D7") (pin "A") (pinfunction "+_A") (pintype "passive"))
      (node (ref "R13") (pin "2") (pinfunction "2_2") (pintype "passive"))
    )
    (net (code "38") (name "Net-(D8-PadA)") (class "Default")
      (node (ref "D8") (pin "A") (pinfunction "A_A") (pintype "passive"))
      (node (ref "R27") (pin "1") (pinfunction "1_1") (pintype "passive"))
    )
    (net (code "39") (name "Net-(D9-PadA)") (class "Default")
      (node (ref "D9") (pin "A") (pinfunction "A_A") (pintype "passive"))
      (node (ref "R28") (pin "1") (pinfunction "1_1") (pintype "passive"))
    )
    (net (code "40") (name "Net-(D10-PadA)") (class "Default")
      (node (ref "D10") (pin "A") (pinfunction "A_A") (pintype "passive"))
      (node (ref "R29") (pin "1") (pinfunction "1_1") (pintype "passive"))
    )
    (net (code "41") (name "Net-(D13-PadA)") (class "Default")
      (node (ref "D13") (pin "A") (pinfunction "A_A") (pintype "passive"))
      (node (ref "R30") (pin "1") (pinfunction "1_1") (pintype "passive"))
    )
    (net (code "42") (name "Net-(D14-PadA)") (class "Default")
      (node (ref "D14") (pin "A") (pinfunction "A_A") (pintype "passive"))
      (node (ref "R32") (pin "1") (pinfunction "1_1") (pintype "passive"))
    )
    (net (code "43") (name "Net-(D15-Pad-)") (class "Default")
      (node (ref "D15") (pin "-") (pinfunction "-_-") (pintype "passive"))
      (node (ref "F1") (pin "1") (pinfunction "1_1") (pintype "bidirectional"))
    )
    (net (code "44") (name "Net-(IC1-IN)") (class "Default")
      (node (ref "C7") (pin "1") (pinfunction "1_1") (pintype "passive"))
      (node (ref "D11") (pin "-") (pinfunction "-_-") (pintype "passive"))
      (node (ref "D12") (pin "-") (pinfunction "-_-") (pintype "passive"))
      (node (ref "IC1") (pin "3") (pinfunction "IN_3") (pintype "input"))
    )
    (net (code "45") (name "Net-(IC1-OUT(1))") (class "Default")
      (node (ref "C1") (pin "1") (pinfunction "1_1") (pintype "passive"))
      (node (ref "D15") (pin "+") (pinfunction "+_+") (pintype "passive"))
      (node (ref "IC1") (pin "2") (pinfunction "OUT(1)_2") (pintype "output"))
    )
    (net (code "46") (name "Net-(IC2-PTD4{slash}LLWU_P14)") (class "Default")
      (node (ref "D5") (pin "C") (pinfunction "C_C") (pintype "passive"))
      (node (ref "IC2") (pin "29") (pinfunction "PTD4/LLWU_P14_29") (pintype "passive"))
    )
    (net (code "47") (name "Net-(IC2-PTD7)") (class "Default")
      (node (ref "IC2") (pin "32") (pinfunction "PTD7_32") (pintype "passive"))
      (node (ref "R23") (pin "1") (pinfunction "1_1") (pintype "passive"))
      (node (ref "R24") (pin "2") (pinfunction "2_2") (pintype "passive"))
    )
    (net (code "48") (name "Net-(IC7-G)") (class "Default")
      (node (ref "IC7") (pin "2") (pinfunction "G_2") (pintype "passive"))
      (node (ref "R3") (pin "1") (pinfunction "1_1") (pintype "passive"))
    )
    (net (code "49") (name "Net-(J2-PadVBUS)") (class "Default")
      (node (ref "J2") (pin "VBUS") (pinfunction "VBUS_VBUS") (pintype "power_in"))
      (node (ref "L1") (pin "1") (pinfunction "1_1") (pintype "passive"))
    )
    (net (code "50") (name "Net-(J2-SHIELD-PadS1)") (class "Default")
      (node (ref "J2") (pin "S1") (pinfunction "SHIELD_S1") (pintype "bidirectional"))
      (node (ref "J2") (pin "S2") (pinfunction "SHIELD_S2") (pintype "bidirectional"))
      (node (ref "J2") (pin "S3") (pinfunction "SHIELD_S3") (pintype "bidirectional"))
      (node (ref "J2") (pin "S4") (pinfunction "SHIELD_S4") (pintype "bidirectional"))
      (node (ref "L2") (pin "1") (pinfunction "1_1") (pintype "passive"))
    )
    (net (code "51") (name "Net-(U$1-EXTAL32)") (class "Default")
      (node (ref "U$1") (pin "20") (pinfunction "EXTAL32_20") (pintype "bidirectional"))
      (node (ref "Y1") (pin "1") (pinfunction "1_1") (pintype "passive"))
    )
    (net (code "52") (name "Net-(U$1-OSC1)") (class "Default")
      (node (ref "U$1") (pin "32") (pinfunction "OSC1_32") (pintype "bidirectional"))
      (node (ref "Y2") (pin "3") (pinfunction "2_3") (pintype "passive"))
    )
    (net (code "53") (name "Net-(U$1-OSC2)") (class "Default")
      (node (ref "U$1") (pin "33") (pinfunction "OSC2_33") (pintype "bidirectional"))
      (node (ref "Y2") (pin "1") (pinfunction "1_1") (pintype "passive"))
    )
    (net (code "54") (name "Net-(U$1-XTAL32)") (class "Default")
      (node (ref "U$1") (pin "19") (pinfunction "XTAL32_19") (pintype "bidirectional"))
      (node (ref "Y1") (pin "2") (pinfunction "2_2") (pintype "passive"))
    )
    (net (code "55") (name "Net-(U$3-P$3)") (class "Default")
      (node (ref "9V_COINCELL_BATTERY") (pin "V-") (pinfunction "V-_V-") (pintype "bidirectional"))
      (node (ref "U$3") (pin "3") (pinfunction "P$3_3") (pintype "bidirectional"))
    )
    (net (code "56") (name "Net-(U$3-P$4)") (class "Default")
      (node (ref "9V_COINCELL_BATTERY") (pin "V+") (pinfunction "V+_V+") (pintype "bidirectional"))
      (node (ref "U$3") (pin "4") (pinfunction "P$4_4") (pintype "bidirectional"))
    )
    (net (code "57") (name "Net-(U2-1Z)") (class "Default")
      (node (ref "CT1_VPOT") (pin "3") (pinfunction "3_3") (pintype "passive"))
      (node (ref "R27") (pin "2") (pinfunction "2_2") (pintype "passive"))
      (node (ref "U2") (pin "2") (pinfunction "1Z_2") (pintype "bidirectional"))
      (node (ref "U3") (pin "8") (pinfunction "P$V+_8") (pintype "bidirectional"))
    )
    (net (code "58") (name "Net-(U2-2Z)") (class "Default")
      (node (ref "CT2_VPOT") (pin "3") (pinfunction "3_3") (pintype "passive"))
      (node (ref "R28") (pin "2") (pinfunction "2_2") (pintype "passive"))
      (node (ref "U2") (pin "3") (pinfunction "2Z_3") (pintype "bidirectional"))
      (node (ref "U4") (pin "8") (pinfunction "P$V+_8") (pintype "bidirectional"))
    )
    (net (code "59") (name "Net-(U2-3Z)") (class "Default")
      (node (ref "CT3_VPOT") (pin "3") (pinfunction "3_3") (pintype "passive"))
      (node (ref "R29") (pin "2") (pinfunction "2_2") (pintype "passive"))
      (node (ref "U2") (pin "9") (pinfunction "3Z_9") (pintype "bidirectional"))
      (node (ref "U5") (pin "8") (pinfunction "P$V+_8") (pintype "bidirectional"))
    )
    (net (code "60") (name "Net-(U2-4Z)") (class "Default")
      (node (ref "CT4_VPOT") (pin "3") (pinfunction "3_3") (pintype "passive"))
      (node (ref "R30") (pin "2") (pinfunction "2_2") (pintype "passive"))
      (node (ref "U2") (pin "10") (pinfunction "4Z_10") (pintype "bidirectional"))
      (node (ref "U6") (pin "8") (pinfunction "P$V+_8") (pintype "bidirectional"))
    )
    (net (code "61") (name "Net-(U3A-+IN)") (class "Default")
      (node (ref "CT1_APOT") (pin "1") (pinfunction "1_1") (pintype "passive"))
      (node (ref "CT1_BPOT") (pin "2") (pinfunction "2_2") (pintype "passive"))
      (node (ref "CT1_VPOT") (pin "2") (pinfunction "2_2") (pintype "passive"))
      (node (ref "R11") (pin "2") (pinfunction "2_2") (pintype "passive"))
      (node (ref "R12") (pin "2") (pinfunction "2_2") (pintype "passive"))
      (node (ref "U3") (pin "2") (pinfunction "-IN_2") (pintype "input"))
      (node (ref "U3") (pin "3") (pinfunction "+IN_3") (pintype "input"))
    )
    (net (code "62") (name "Net-(U4A-+IN)") (class "Default")
      (node (ref "CT2_VPOT") (pin "2") (pinfunction "2_2") (pintype "passive"))
      (node (ref "R14") (pin "2") (pinfunction "2_2") (pintype "passive"))
      (node (ref "R15") (pin "2") (pinfunction "2_2") (pintype "passive"))
      (node (ref "U4") (pin "3") (pinfunction "+IN_3") (pintype "input"))
    )
    (net (code "63") (name "Net-(U4A--IN)") (class "Default")
      (node (ref "CT2_APOT") (pin "1") (pinfunction "1_1") (pintype "passive"))
      (node (ref "CT2_BPOT") (pin "2") (pinfunction "2_2") (pintype "passive"))
      (node (ref "U4") (pin "2") (pinfunction "-IN_2") (pintype "input"))
    )
    (net (code "64") (name "Net-(U5A-+IN)") (class "Default")
      (node (ref "CT3_VPOT") (pin "2") (pinfunction "2_2") (pintype "passive"))
      (node (ref "R17") (pin "2") (pinfunction "2_2") (pintype "passive"))
      (node (ref "R18") (pin "2") (pinfunction "2_2") (pintype "passive"))
      (node (ref "U5") (pin "3") (pinfunction "+IN_3") (pintype "input"))
    )
    (net (code "65") (name "Net-(U5A--IN)") (class "Default")
      (node (ref "CT3_APOT") (pin "1") (pinfunction "1_1") (pintype "passive"))
      (node (ref "CT3_BPOT") (pin "2") (pinfunction "2_2") (pintype "passive"))
      (node (ref "U5") (pin "2") (pinfunction "-IN_2") (pintype "input"))
    )
    (net (code "66") (name "Net-(U6A-+IN)") (class "Default")
      (node (ref "CT4_VPOT") (pin "2") (pinfunction "2_2") (pintype "passive"))
      (node (ref "R20") (pin "2") (pinfunction "2_2") (pintype "passive"))
      (node (ref "R21") (pin "2") (pinfunction "2_2") (pintype "passive"))
      (node (ref "U6") (pin "3") (pinfunction "+IN_3") (pintype "input"))
    )
    (net (code "67") (name "Net-(U6A--IN)") (class "Default")
      (node (ref "CT4_APOT") (pin "1") (pinfunction "1_1") (pintype "passive"))
      (node (ref "CT4_BPOT") (pin "2") (pinfunction "2_2") (pintype "passive"))
      (node (ref "U6") (pin "2") (pinfunction "-IN_2") (pintype "input"))
    )
    (net (code "68") (name "Net-(XB2-~{RESET})") (class "Default")
      (node (ref "S1") (pin "1") (pinfunction "1_1") (pintype "passive"))
      (node (ref "XB2") (pin "5") (pinfunction "~{RESET}_5") (pintype "input"))
    )
    (net (code "69") (name "P5-9V_VINB") (class "Default")
      (node (ref "D11") (pin "+") (pinfunction "+_+") (pintype "passive"))
    )
    (net (code "70") (name "P5-9V_VINM") (class "Default")
      (node (ref "FRDM1") (pin "J9_16") (pinfunction "P5-9V_VIN_J9_16") (pintype "bidirectional"))
      (node (ref "U$3") (pin "1") (pinfunction "P$1_1") (pintype "bidirectional"))
    )
    (net (code "71") (name "P5V_SDA") (class "Default")
      (node (ref "C5") (pin "1") (pinfunction "1_1") (pintype "passive"))
      (node (ref "D12") (pin "+") (pinfunction "+_+") (pintype "passive"))
      (node (ref "IC2") (pin "6") (pinfunction "VREGIN_6") (pintype "passive"))
      (node (ref "L1") (pin "2") (pinfunction "2_2") (pintype "passive"))
      (node (ref "R23") (pin "2") (pinfunction "2_2") (pintype "passive"))
      (node (ref "R25") (pin "2") (pinfunction "2_2") (pintype "passive"))
    )
    (net (code "72") (name "RST_TGTMCU") (class "Default")
      (node (ref "C2") (pin "1") (pinfunction "1_1") (pintype "passive"))
      (node (ref "IC2") (pin "21") (pinfunction "PTB1_21") (pintype "passive"))
      (node (ref "R31") (pin "1") (pinfunction "1_1") (pintype "passive"))
      (node (ref "S2") (pin "1") (pinfunction "1_1") (pintype "passive"))
      (node (ref "U$6") (pin "10") (pinfunction "~{RESET}_10") (pintype "bidirectional"))
    )
    (net (code "73") (name "SDA_EXTAL") (class "Default")
      (node (ref "IC2") (pin "17") (pinfunction "PTA18_17") (pintype "passive"))
      (node (ref "Y3") (pin "3") (pinfunction "2_3") (pintype "passive"))
    )
    (net (code "74") (name "SDA_JTAG_TCLK") (class "Default")
      (node (ref "IC2") (pin "12") (pinfunction "PTA0_12") (pintype "passive"))
      (node (ref "U$2") (pin "4") (pinfunction "SWDCLK/TCK_4") (pintype "bidirectional"))
    )
    (net (code "75") (name "SDA_JTAG_TDI") (class "Default")
      (node (ref "IC2") (pin "13") (pinfunction "PTA1_13") (pintype "passive"))
      (node (ref "U$2") (pin "8") (pinfunction "NC/TDI_8") (pintype "bidirectional"))
    )
    (net (code "76") (name "SDA_JTAG_TDO") (class "Default")
      (node (ref "IC2") (pin "14") (pinfunction "PTA2_14") (pintype "passive"))
      (node (ref "U$2") (pin "6") (pinfunction "SWO/TDO_6") (pintype "bidirectional"))
    )
    (net (code "77") (name "SDA_JTAG_TMS") (class "Default")
      (node (ref "IC2") (pin "15") (pinfunction "PTA3_15") (pintype "passive"))
      (node (ref "R9") (pin "2") (pinfunction "2_2") (pintype "passive"))
      (node (ref "U$2") (pin "2") (pinfunction "SWDIO/TMS_2") (pintype "bidirectional"))
    )
    (net (code "78") (name "SDA_PTD6") (class "Default")
      (node (ref "IC2") (pin "31") (pinfunction "PTD6/LLWU_P15_31") (pintype "passive"))
      (node (ref "U$1") (pin "35") (pinfunction "D16/A2/TOUCH_35") (pintype "bidirectional"))
    )
    (net (code "79") (name "SDA_RST") (class "Default")
      (node (ref "IC2") (pin "19") (pinfunction "RESET_B_19") (pintype "passive"))
      (node (ref "R25") (pin "1") (pinfunction "1_1") (pintype "passive"))
      (node (ref "R26") (pin "2") (pinfunction "2_2") (pintype "passive"))
      (node (ref "U$2") (pin "10") (pinfunction "~{RESET}_10") (pintype "bidirectional"))
    )
    (net (code "80") (name "SDA_SPIO_SCK") (class "Default")
      (node (ref "IC2") (pin "26") (pinfunction "PTC5/LLWU_P9_26") (pintype "passive"))
      (node (ref "U1") (pin "12") (pinfunction "4A_12") (pintype "input"))
    )
    (net (code "81") (name "SDA_SPIO_SIN") (class "Default")
      (node (ref "IC2") (pin "28") (pinfunction "PTC7_28") (pintype "passive"))
      (node (ref "U1") (pin "8") (pinfunction "3Y_8") (pintype "output"))
    )
    (net (code "82") (name "SDA_SWD_EN") (class "Default")
      (node (ref "IC2") (pin "16") (pinfunction "PTA4/LLWU_P3_16") (pintype "passive"))
      (node (ref "R6") (pin "1") (pinfunction "1_1") (pintype "passive"))
      (node (ref "U1") (pin "10") (pinfunction "3~{OE}_10") (pintype "input"))
      (node (ref "U1") (pin "13") (pinfunction "4~{OE}_13") (pintype "input"))
    )
    (net (code "83") (name "SDA_USB_VOUT33") (class "Default")
      (node (ref "C14") (pin "2") (pinfunction "2_2") (pintype "passive"))
      (node (ref "IC2") (pin "5") (pinfunction "VOUT33_5") (pintype "passive"))
    )
    (net (code "84") (name "SDA_XTAL") (class "Default")
      (node (ref "IC2") (pin "18") (pinfunction "PTA19_18") (pintype "passive"))
      (node (ref "Y3") (pin "1") (pinfunction "1_1") (pintype "passive"))
    )
    (net (code "85") (name "SLPB") (class "Default")
      (node (ref "FRDM1") (pin "J19_13") (pinfunction "PTD7_J19_13") (pintype "bidirectional"))
      (node (ref "U$1") (pin "46") (pinfunction "D9/RX2/PWM_46") (pintype "bidirectional"))
    )
    (net (code "86") (name "SPI0_SOUT") (class "Default")
      (node (ref "IC2") (pin "27") (pinfunction "PTC6/LLWU_P10_27") (pintype "passive"))
      (node (ref "U1") (pin "2") (pinfunction "1A_2") (pintype "input"))
    )
    (net (code "87") (name "SWD_CLK_TGTMCU") (class "Default")
      (node (ref "U$6") (pin "4") (pinfunction "SWDCLK/TCK_4") (pintype "bidirectional"))
      (node (ref "U1") (pin "11") (pinfunction "4Y_11") (pintype "output"))
    )
    (net (code "88") (name "SWD_DIO_TGTMCU") (class "Default")
      (node (ref "U$1") (pin "25") (pinfunction "PTA3_25") (pintype "bidirectional"))
      (node (ref "U$6") (pin "2") (pinfunction "SWDIO/TMS_2") (pintype "bidirectional"))
      (node (ref "U1") (pin "3") (pinfunction "1Y_3") (pintype "output"))
      (node (ref "U1") (pin "9") (pinfunction "3A_9") (pintype "input"))
    )
    (net (code "89") (name "UART1RX_TGTMCU") (class "Default")
      (node (ref "IC2") (pin "25") (pinfunction "PTC4/LLWU_P8_25") (pintype "passive"))
      (node (ref "R7") (pin "2") (pinfunction "2_2") (pintype "passive"))
    )
    (net (code "90") (name "UART1TX_TGTMCU") (class "Default")
      (node (ref "IC2") (pin "24") (pinfunction "PTC3/LLWU_P7_24") (pintype "passive"))
      (node (ref "R8") (pin "2") (pinfunction "2_2") (pintype "passive"))
    )
    (net (code "91") (name "UART1_RXB") (class "Default")
      (node (ref "FRDM1") (pin "J19_1") (pinfunction "PTD0_J19_1") (pintype "bidirectional"))
      (node (ref "U$1") (pin "2") (pinfunction "D26_2") (pintype "bidirectional"))
    )
    (net (code "92") (name "UART1_RXM") (class "Default")
      (node (ref "FRDM1") (pin "J19_2") (pinfunction "D0/PTE1_J19_2") (pintype "bidirectional"))
      (node (ref "XB2") (pin "2") (pinfunction "DOUT_2") (pintype "output"))
    )
    (net (code "93") (name "UART1_TXB") (class "Default")
      (node (ref "FRDM1") (pin "J19_3") (pinfunction "PTC11_J19_3") (pintype "bidirectional"))
      (node (ref "U$1") (pin "1") (pinfunction "D31_1") (pintype "bidirectional"))
    )
    (net (code "94") (name "UART1_TXM") (class "Default")
      (node (ref "FRDM1") (pin "J19_4") (pinfunction "D1/PTE0_J19_4") (pintype "bidirectional"))
      (node (ref "XB2") (pin "3") (pinfunction "DIN/~{CONFIG}_3") (pintype "input"))
    )
    (net (code "95") (name "VCCB") (class "Default")
      (node (ref "C10") (pin "1") (pinfunction "1_1") (pintype "passive"))
      (node (ref "C11") (pin "1") (pinfunction "1_1") (pintype "passive"))
      (node (ref "C12") (pin "1") (pinfunction "1_1") (pintype "passive"))
      (node (ref "C13") (pin "1") (pinfunction "1_1") (pintype "passive"))
      (node (ref "C16") (pin "1") (pinfunction "1_1") (pintype "passive"))
      (node (ref "C3") (pin "1") (pinfunction "1_1") (pintype "passive"))
      (node (ref "C4") (pin "2") (pinfunction "2_2") (pintype "passive"))
      (node (ref "C6") (pin "1") (pinfunction "1_1") (pintype "passive"))
      (node (ref "C8") (pin "1") (pinfunction "1_1") (pintype "passive"))
      (node (ref "C9") (pin "1") (pinfunction "1_1") (pintype "passive"))
      (node (ref "D2") (pin "C") (pinfunction "-_C") (pintype "passive"))
      (node (ref "F1") (pin "2") (pinfunction "2_2") (pintype "bidirectional"))
      (node (ref "IC2") (pin "1") (pinfunction "VDD_1") (pintype "passive"))
      (node (ref "IC2") (pin "7") (pinfunction "VDDA_7") (pintype "passive"))
      (node (ref "IC7") (pin "1") (pinfunction "K_1") (pintype "passive"))
      (node (ref "R10") (pin "2") (pinfunction "2_2") (pintype "passive"))
      (node (ref "R31") (pin "2") (pinfunction "2_2") (pintype "passive"))
      (node (ref "R32") (pin "2") (pinfunction "2_2") (pintype "passive"))
      (node (ref "R5") (pin "2") (pinfunction "2_2") (pintype "passive"))
      (node (ref "R6") (pin "2") (pinfunction "2_2") (pintype "passive"))
      (node (ref "R9") (pin "1") (pinfunction "1_1") (pintype "passive"))
      (node (ref "U$1") (pin "13") (pinfunction "VCCA_13") (pintype "bidirectional"))
      (node (ref "U$1") (pin "14") (pinfunction "VREF-H_14") (pintype "bidirectional"))
      (node (ref "U$1") (pin "3") (pinfunction "VCC_3") (pintype "bidirectional"))
      (node (ref "U$1") (pin "30") (pinfunction "VCC_30") (pintype "bidirectional"))
      (node (ref "U$1") (pin "48") (pinfunction "VCC_48") (pintype "bidirectional"))
      (node (ref "U$2") (pin "1") (pinfunction "VCC_1") (pintype "bidirectional"))
      (node (ref "U$6") (pin "1") (pinfunction "VCC_1") (pintype "bidirectional"))
      (node (ref "U1") (pin "14") (pinfunction "VCC_14") (pintype "power_in"))
    )
    (net (code "96") (name "VCCM") (class "Default")
      (node (ref "FRDM1") (pin "J9_8") (pinfunction "P3V3_1_J9_8") (pintype "bidirectional"))
      (node (ref "U2") (pin "1") (pinfunction "1Y_1") (pintype "bidirectional"))
      (node (ref "U2") (pin "11") (pinfunction "4Y_11") (pintype "bidirectional"))
      (node (ref "U2") (pin "4") (pinfunction "2Y_4") (pintype "bidirectional"))
      (node (ref "U2") (pin "8") (pinfunction "3Y_8") (pintype "bidirectional"))
      (node (ref "XB2") (pin "1") (pinfunction "VCC_1") (pintype "power_in"))
    )
    (net (code "97") (name "unconnected-(CT1_APOT-Pad3)") (class "Default")
      (node (ref "CT1_APOT") (pin "3") (pinfunction "3_3") (pintype "passive"))
    )
    (net (code "98") (name "unconnected-(CT1_BPOT-Pad1)") (class "Default")
      (node (ref "CT1_BPOT") (pin "1") (pinfunction "1_1") (pintype "passive"))
    )
    (net (code "99") (name "unconnected-(CT1_VPOT-Pad1)") (class "Default")
      (node (ref "CT1_VPOT") (pin "1") (pinfunction "1_1") (pintype "passive"))
    )
    (net (code "100") (name "unconnected-(CT2_APOT-Pad3)") (class "Default")
      (node (ref "CT2_APOT") (pin "3") (pinfunction "3_3") (pintype "passive"))
    )
    (net (code "101") (name "unconnected-(CT2_BPOT-Pad1)") (class "Default")
      (node (ref "CT2_BPOT") (pin "1") (pinfunction "1_1") (pintype "passive"))
    )
    (net (code "102") (name "unconnected-(CT2_VPOT-Pad1)") (class "Default")
      (node (ref "CT2_VPOT") (pin "1") (pinfunction "1_1") (pintype "passive"))
    )
    (net (code "103") (name "unconnected-(CT3_APOT-Pad3)") (class "Default")
      (node (ref "CT3_APOT") (pin "3") (pinfunction "3_3") (pintype "passive"))
    )
    (net (code "104") (name "unconnected-(CT3_BPOT-Pad1)") (class "Default")
      (node (ref "CT3_BPOT") (pin "1") (pinfunction "1_1") (pintype "passive"))
    )
    (net (code "105") (name "unconnected-(CT3_VPOT-Pad1)") (class "Default")
      (node (ref "CT3_VPOT") (pin "1") (pinfunction "1_1") (pintype "passive"))
    )
    (net (code "106") (name "unconnected-(CT4_APOT-Pad3)") (class "Default")
      (node (ref "CT4_APOT") (pin "3") (pinfunction "3_3") (pintype "passive"))
    )
    (net (code "107") (name "unconnected-(CT4_BPOT-Pad1)") (class "Default")
      (node (ref "CT4_BPOT") (pin "1") (pinfunction "1_1") (pintype "passive"))
    )
    (net (code "108") (name "unconnected-(CT4_VPOT-Pad1)") (class "Default")
      (node (ref "CT4_VPOT") (pin "1") (pinfunction "1_1") (pintype "passive"))
    )
    (net (code "109") (name "unconnected-(FRDM1-A0{slash}PTC0-PadJ10_2)") (class "Default")
      (node (ref "FRDM1") (pin "J10_2") (pinfunction "A0/PTC0_J10_2") (pintype "bidirectional"))
    )
    (net (code "110") (name "unconnected-(FRDM1-A1{slash}PTC1-PadJ10_4)") (class "Default")
      (node (ref "FRDM1") (pin "J10_4") (pinfunction "A1/PTC1_J10_4") (pintype "bidirectional"))
    )
    (net (code "111") (name "unconnected-(FRDM1-AREF{slash}VREFH-PadJ2_16)") (class "Default")
      (node (ref "FRDM1") (pin "J2_16") (pinfunction "AREF/VREFH_J2_16") (pintype "bidirectional"))
    )
    (net (code "112") (name "unconnected-(FRDM1-CMP0_IN5-PadJ10_1)") (class "Default")
      (node (ref "FRDM1") (pin "J10_1") (pinfunction "CMP0_IN5_J10_1") (pintype "bidirectional"))
    )
    (net (code "113") (name "unconnected-(FRDM1-CMP1_IN3-PadJ10_3)") (class "Default")
      (node (ref "FRDM1") (pin "J10_3") (pinfunction "CMP1_IN3_J10_3") (pintype "bidirectional"))
    )
    (net (code "114") (name "unconnected-(FRDM1-D5{slash}PTA1-PadJ19_12)") (class "Default")
      (node (ref "FRDM1") (pin "J19_12") (pinfunction "D5/PTA1_J19_12") (pintype "bidirectional"))
    )
    (net (code "115") (name "unconnected-(FRDM1-D9{slash}PTA2-PadJ2_4)") (class "Default")
      (node (ref "FRDM1") (pin "J2_4") (pinfunction "D9/PTA2_J2_4") (pintype "bidirectional"))
    )
    (net (code "116") (name "unconnected-(FRDM1-D10{slash}PTC2-PadJ2_6)") (class "Default")
      (node (ref "FRDM1") (pin "J2_6") (pinfunction "D10/PTC2_J2_6") (pintype "bidirectional"))
    )
    (net (code "117") (name "unconnected-(FRDM1-D11{slash}PTD2-PadJ2_8)") (class "Default")
      (node (ref "FRDM1") (pin "J2_8") (pinfunction "D11/PTD2_J2_8") (pintype "bidirectional"))
    )
    (net (code "118") (name "unconnected-(FRDM1-D12{slash}PTD3-PadJ2_10)") (class "Default")
      (node (ref "FRDM1") (pin "J2_10") (pinfunction "D12/PTD3_J2_10") (pintype "bidirectional"))
    )
    (net (code "119") (name "unconnected-(FRDM1-D13{slash}PTD1-PadJ2_12)") (class "Default")
      (node (ref "FRDM1") (pin "J2_12") (pinfunction "D13/PTD1_J2_12") (pintype "bidirectional"))
    )
    (net (code "120") (name "unconnected-(FRDM1-GND_2-PadJ2_14)") (class "Default")
      (node (ref "FRDM1") (pin "J2_14") (pinfunction "GND_2_J2_14") (pintype "bidirectional"))
    )
    (net (code "121") (name "unconnected-(FRDM1-P3V3_0-PadJ9_4)") (class "Default")
      (node (ref "FRDM1") (pin "J9_4") (pinfunction "P3V3_0_J9_4") (pintype "bidirectional"))
    )
    (net (code "122") (name "unconnected-(FRDM1-P5V_USB-PadJ9_10)") (class "Default")
      (node (ref "FRDM1") (pin "J9_10") (pinfunction "P5V_USB_J9_10") (pintype "bidirectional"))
    )
    (net (code "123") (name "unconnected-(FRDM1-PTA4-PadJ19_11)") (class "Default")
      (node (ref "FRDM1") (pin "J19_11") (pinfunction "PTA4_J19_11") (pintype "bidirectional"))
    )
    (net (code "124") (name "unconnected-(FRDM1-PTC10-PadJ2_3)") (class "Default")
      (node (ref "FRDM1") (pin "J2_3") (pinfunction "PTC10_J2_3") (pintype "bidirectional"))
    )
    (net (code "125") (name "unconnected-(FRDM1-RST_TGTMCU-PadJ9_6)") (class "Default")
      (node (ref "FRDM1") (pin "J9_6") (pinfunction "RST_TGTMCU_J9_6") (pintype "bidirectional"))
    )
    (net (code "126") (name "unconnected-(FRDM1-SCL{slash}PTB2-PadJ2_20)") (class "Default")
      (node (ref "FRDM1") (pin "J2_20") (pinfunction "SCL/PTB2_J2_20") (pintype "bidirectional"))
    )
    (net (code "127") (name "unconnected-(FRDM1-SDA_PTD5-PadJ9_2)") (class "Default")
      (node (ref "FRDM1") (pin "J9_2") (pinfunction "SDA_PTD5_J9_2") (pintype "bidirectional"))
    )
    (net (code "128") (name "unconnected-(FRDM1-SDA{slash}PTB3-PadJ2_18)") (class "Default")
      (node (ref "FRDM1") (pin "J2_18") (pinfunction "SDA/PTB3_J2_18") (pintype "bidirectional"))
    )
    (net (code "129") (name "unconnected-(IC1-OUT(2)-Pad4)") (class "Default")
      (node (ref "IC1") (pin "4") (pinfunction "OUT(2)_4") (pintype "output"))
    )
    (net (code "130") (name "unconnected-(IC2-EXTAL32-Pad10)") (class "Default")
      (node (ref "IC2") (pin "10") (pinfunction "EXTAL32_10") (pintype "passive"))
    )
    (net (code "131") (name "unconnected-(IC2-PTC1{slash}LLWU_P6-Pad22)") (class "Default")
      (node (ref "IC2") (pin "22") (pinfunction "PTC1/LLWU_P6_22") (pintype "passive"))
    )
    (net (code "132") (name "unconnected-(IC2-PTC2-Pad23)") (class "Default")
      (node (ref "IC2") (pin "23") (pinfunction "PTC2_23") (pintype "passive"))
    )
    (net (code "133") (name "unconnected-(IC2-PTD5-Pad30)") (class "Default")
      (node (ref "IC2") (pin "30") (pinfunction "PTD5_30") (pintype "passive"))
    )
    (net (code "134") (name "unconnected-(IC2-VBAT-Pad11)") (class "Default")
      (node (ref "IC2") (pin "11") (pinfunction "VBAT_11") (pintype "passive"))
    )
    (net (code "135") (name "unconnected-(IC2-XTAL32-Pad9)") (class "Default")
      (node (ref "IC2") (pin "9") (pinfunction "XTAL32_9") (pintype "passive"))
    )
    (net (code "136") (name "unconnected-(J2-PadID)") (class "Default")
      (node (ref "J2") (pin "ID") (pinfunction "ID_ID") (pintype "bidirectional"))
    )
    (net (code "137") (name "unconnected-(U$1-CMP1{slash}DNC-Pad18)") (class "Default")
      (node (ref "U$1") (pin "18") (pinfunction "CMP1/DNC_18") (pintype "bidirectional"))
    )
    (net (code "138") (name "unconnected-(U$1-D2-Pad57)") (class "Default")
      (node (ref "U$1") (pin "57") (pinfunction "D2_57") (pintype "bidirectional"))
    )
    (net (code "139") (name "unconnected-(U$1-D4{slash}PWM-Pad29)") (class "Default")
      (node (ref "U$1") (pin "29") (pinfunction "D4/PWM_29") (pintype "bidirectional"))
    )
    (net (code "140") (name "unconnected-(U$1-D5{slash}PWM-Pad64)") (class "Default")
      (node (ref "U$1") (pin "64") (pinfunction "D5/PWM_64") (pintype "bidirectional"))
    )
    (net (code "141") (name "unconnected-(U$1-D7{slash}RX3-Pad59)") (class "Default")
      (node (ref "U$1") (pin "59") (pinfunction "D7/RX3_59") (pintype "bidirectional"))
    )
    (net (code "142") (name "unconnected-(U$1-D8{slash}TX3-Pad60)") (class "Default")
      (node (ref "U$1") (pin "60") (pinfunction "D8/TX3_60") (pintype "bidirectional"))
    )
    (net (code "143") (name "unconnected-(U$1-D11{slash}MOSI-Pad51)") (class "Default")
      (node (ref "U$1") (pin "51") (pinfunction "D11/MOSI_51") (pintype "bidirectional"))
    )
    (net (code "144") (name "unconnected-(U$1-D12{slash}MISO-Pad52)") (class "Default")
      (node (ref "U$1") (pin "52") (pinfunction "D12/MISO_52") (pintype "bidirectional"))
    )
    (net (code "145") (name "unconnected-(U$1-D13{slash}SCK-Pad50)") (class "Default")
      (node (ref "U$1") (pin "50") (pinfunction "D13/SCK_50") (pintype "bidirectional"))
    )
    (net (code "146") (name "unconnected-(U$1-D14{slash}A0-Pad58)") (class "Default")
      (node (ref "U$1") (pin "58") (pinfunction "D14/A0_58") (pintype "bidirectional"))
    )
    (net (code "147") (name "unconnected-(U$1-D15{slash}A1{slash}TOUCH-Pad43)") (class "Default")
      (node (ref "U$1") (pin "43") (pinfunction "D15/A1/TOUCH_43") (pintype "bidirectional"))
    )
    (net (code "148") (name "unconnected-(U$1-D17{slash}A3{slash}TOUCH-Pad36)") (class "Default")
      (node (ref "U$1") (pin "36") (pinfunction "D17/A3/TOUCH_36") (pintype "bidirectional"))
    )
    (net (code "149") (name "unconnected-(U$1-D18{slash}A4{slash}SDA{slash}TOUCH-Pad38)") (class "Default")
      (node (ref "U$1") (pin "38") (pinfunction "D18/A4/SDA/TOUCH_38") (pintype "bidirectional"))
    )
    (net (code "150") (name "unconnected-(U$1-D19{slash}A5{slash}SCL{slash}TOUCH-Pad37)") (class "Default")
      (node (ref "U$1") (pin "37") (pinfunction "D19/A5/SCL/TOUCH_37") (pintype "bidirectional"))
    )
    (net (code "151") (name "unconnected-(U$1-D20{slash}A6{slash}PWM-Pad62)") (class "Default")
      (node (ref "U$1") (pin "62") (pinfunction "D20/A6/PWM_62") (pintype "bidirectional"))
    )
    (net (code "152") (name "unconnected-(U$1-D21{slash}A7{slash}PWM-Pad63)") (class "Default")
      (node (ref "U$1") (pin "63") (pinfunction "D21/A7/PWM_63") (pintype "bidirectional"))
    )
    (net (code "153") (name "unconnected-(U$1-D22{slash}A8{slash}PWM{slash}TOUCH-Pad44)") (class "Default")
      (node (ref "U$1") (pin "44") (pinfunction "D22/A8/PWM/TOUCH_44") (pintype "bidirectional"))
    )
    (net (code "154") (name "unconnected-(U$1-D23{slash}A9{slash}PWM{slash}TOUCH-Pad45)") (class "Default")
      (node (ref "U$1") (pin "45") (pinfunction "D23/A9/PWM/TOUCH_45") (pintype "bidirectional"))
    )
    (net (code "155") (name "unconnected-(U$1-D25{slash}TOUCH-Pad42)") (class "Default")
      (node (ref "U$1") (pin "42") (pinfunction "D25/TOUCH_42") (pintype "bidirectional"))
    )
    (net (code "156") (name "unconnected-(U$1-D27-Pad54)") (class "Default")
      (node (ref "U$1") (pin "54") (pinfunction "D27_54") (pintype "bidirectional"))
    )
    (net (code "157") (name "unconnected-(U$1-D29-Pad55)") (class "Default")
      (node (ref "U$1") (pin "55") (pinfunction "D29_55") (pintype "bidirectional"))
    )
    (net (code "158") (name "unconnected-(U$1-D30-Pad56)") (class "Default")
      (node (ref "U$1") (pin "56") (pinfunction "D30_56") (pintype "bidirectional"))
    )
    (net (code "159") (name "unconnected-(U$1-D32{slash}TOUCH-Pad41)") (class "Default")
      (node (ref "U$1") (pin "41") (pinfunction "D32/TOUCH_41") (pintype "bidirectional"))
    )
    (net (code "160") (name "unconnected-(U$1-D33{slash}TOUCH-Pad26)") (class "Default")
      (node (ref "U$1") (pin "26") (pinfunction "D33/TOUCH_26") (pintype "bidirectional"))
    )
    (net (code "161") (name "unconnected-(U$1-PTA0-Pad22)") (class "Default")
      (node (ref "U$1") (pin "22") (pinfunction "PTA0_22") (pintype "bidirectional"))
    )
    (net (code "162") (name "unconnected-(U$1-PTA1-Pad23)") (class "Default")
      (node (ref "U$1") (pin "23") (pinfunction "PTA1_23") (pintype "bidirectional"))
    )
    (net (code "163") (name "unconnected-(U$1-PTA2-Pad24)") (class "Default")
      (node (ref "U$1") (pin "24") (pinfunction "PTA2_24") (pintype "bidirectional"))
    )
    (net (code "164") (name "unconnected-(U$1-RESET-Pad34)") (class "Default")
      (node (ref "U$1") (pin "34") (pinfunction "RESET_34") (pintype "bidirectional"))
    )
    (net (code "165") (name "unconnected-(U$1-USB-M-Pad6)") (class "Default")
      (node (ref "U$1") (pin "6") (pinfunction "USB-M_6") (pintype "bidirectional"))
    )
    (net (code "166") (name "unconnected-(U$1-USB-P-Pad5)") (class "Default")
      (node (ref "U$1") (pin "5") (pinfunction "USB-P_5") (pintype "bidirectional"))
    )
    (net (code "167") (name "unconnected-(U$1-VBAT-Pad21)") (class "Default")
      (node (ref "U$1") (pin "21") (pinfunction "VBAT_21") (pintype "bidirectional"))
    )
    (net (code "168") (name "unconnected-(U$1-VOUT3V3-Pad7)") (class "Default")
      (node (ref "U$1") (pin "7") (pinfunction "VOUT3V3_7") (pintype "bidirectional"))
    )
    (net (code "169") (name "unconnected-(U$1-VREF_OUT-Pad17)") (class "Default")
      (node (ref "U$1") (pin "17") (pinfunction "VREF_OUT_17") (pintype "bidirectional"))
    )
    (net (code "170") (name "unconnected-(U$1-VREGIN-Pad8)") (class "Default")
      (node (ref "U$1") (pin "8") (pinfunction "VREGIN_8") (pintype "bidirectional"))
    )
    (net (code "171") (name "unconnected-(U$2-GND-DETECT-Pad9)") (class "Default")
      (node (ref "U$2") (pin "9") (pinfunction "GND-DETECT_9") (pintype "bidirectional"))
    )
    (net (code "172") (name "unconnected-(U$6-GND-DETECT-Pad9)") (class "Default")
      (node (ref "U$6") (pin "9") (pinfunction "GND-DETECT_9") (pintype "bidirectional"))
    )
    (net (code "173") (name "unconnected-(U$6-NC{slash}TDI-Pad8)") (class "Default")
      (node (ref "U$6") (pin "8") (pinfunction "NC/TDI_8") (pintype "bidirectional"))
    )
    (net (code "174") (name "unconnected-(U$6-SWO{slash}TDO-Pad6)") (class "Default")
      (node (ref "U$6") (pin "6") (pinfunction "SWO/TDO_6") (pintype "bidirectional"))
    )
    (net (code "175") (name "unconnected-(U1-2A-Pad5)") (class "Default")
      (node (ref "U1") (pin "5") (pinfunction "2A_5") (pintype "input"))
    )
    (net (code "176") (name "unconnected-(U1-2Y-Pad6)") (class "Default")
      (node (ref "U1") (pin "6") (pinfunction "2Y_6") (pintype "output"))
    )
    (net (code "177") (name "unconnected-(U1-2~{OE}-Pad4)") (class "Default")
      (node (ref "U1") (pin "4") (pinfunction "2~{OE}_4") (pintype "input"))
    )
    (net (code "178") (name "unconnected-(XB2-AD0{slash}DIO0-Pad20)") (class "Default")
      (node (ref "XB2") (pin "20") (pinfunction "AD0/DIO0_20") (pintype "bidirectional"))
    )
    (net (code "179") (name "unconnected-(XB2-AD1{slash}DIO1-Pad19)") (class "Default")
      (node (ref "XB2") (pin "19") (pinfunction "AD1/DIO1_19") (pintype "bidirectional"))
    )
    (net (code "180") (name "unconnected-(XB2-AD2{slash}DIO2-Pad18)") (class "Default")
      (node (ref "XB2") (pin "18") (pinfunction "AD2/DIO2_18") (pintype "bidirectional"))
    )
    (net (code "181") (name "unconnected-(XB2-ASSOC{slash}AD5{slash}DIO5-Pad15)") (class "Default")
      (node (ref "XB2") (pin "15") (pinfunction "ASSOC/AD5/DIO5_15") (pintype "bidirectional"))
    )
    (net (code "182") (name "unconnected-(XB2-CD{slash}DOUT_EN{slash}DO8-Pad4)") (class "Default")
      (node (ref "XB2") (pin "4") (pinfunction "CD/DOUT_EN/DO8_4") (pintype "output"))
    )
    (net (code "183") (name "unconnected-(XB2-COORD_SEL{slash}AD3{slash}DIO3-Pad17)") (class "Default")
      (node (ref "XB2") (pin "17") (pinfunction "COORD_SEL/AD3/DIO3_17") (pintype "bidirectional"))
    )
    (net (code "184") (name "unconnected-(XB2-PWM0{slash}RSSI-Pad6)") (class "Default")
      (node (ref "XB2") (pin "6") (pinfunction "PWM0/RSSI_6") (pintype "output"))
    )
    (net (code "185") (name "unconnected-(XB2-RF_TX{slash}AD4{slash}DIO4-Pad11)") (class "Default")
      (node (ref "XB2") (pin "11") (pinfunction "RF_TX/AD4/DIO4_11") (pintype "bidirectional"))
    )
    (net (code "186") (name "unconnected-(XB2-VREF-Pad14)") (class "Default")
      (node (ref "XB2") (pin "14") (pinfunction "VREF_14") (pintype "input"))
    )
    (net (code "187") (name "unconnected-(XB2-~{CTS}{slash}DIO7-Pad12)") (class "Default")
      (node (ref "XB2") (pin "12") (pinfunction "~{CTS}/DIO7_12") (pintype "bidirectional"))
    )
    (net (code "188") (name "unconnected-(XB2-~{DTR}{slash}SLEEP_RQ{slash}DI8-Pad9)") (class "Default")
      (node (ref "XB2") (pin "9") (pinfunction "~{DTR}/SLEEP_RQ/DI8_9") (pintype "bidirectional"))
    )
    (net (code "189") (name "unconnected-(XB2-~{RTS}{slash}AD6{slash}DIO6-Pad16)") (class "Default")
      (node (ref "XB2") (pin "16") (pinfunction "~{RTS}/AD6/DIO6_16") (pintype "bidirectional"))
    )
  )
)
